# Sensors.net
KiCad netlist of a schematic drawn in Altium Designer
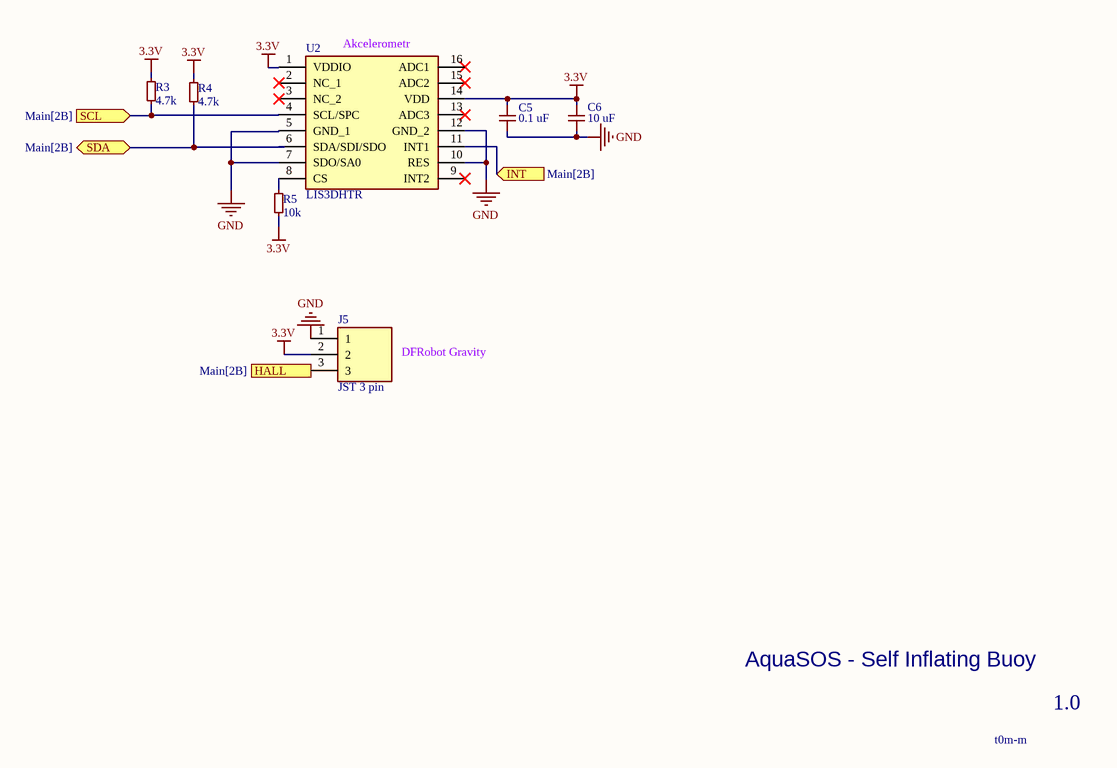
[diagram p0: Sensors.SchDoc]

(export (version "E")
  (design (tool "Eeschema 10.0.6"))
  (components
    (comp (ref "C5")
      (value "0.1 uF")
      (footprint "MLASU105SB7104KFNB25")
      (description "0.1uF Capacitor")
      (libsource (lib "Schlib1") (part "MLASU105SB7104KFNB25"))
    )
    (comp (ref "C6")
      (value "10 uF")
      (footprint "KGM05CS60J106MH")
      (description "10 uF Capacitor")
      (libsource (lib "Schlib1") (part "KGM05CS60J106MH"))
    )
    (comp (ref "J5")
      (value "JST 3 pin")
      (footprint "S3B-PH-K-S")
      (description "JST 3 pin connector")
      (libsource (lib "AquaSOS DevBoard") (part "JST 3 pin"))
    )
    (comp (ref "R3")
      (value "4.7k")
      (footprint "CRCW040210K0FKEDC")
      (description "4.7k 0402 resistor")
      (libsource (lib "") (part "RC0402FR-7D4K7L_1"))
    )
    (comp (ref "R4")
      (value "4.7k")
      (footprint "CRCW040210K0FKEDC")
      (description "4.7k 0402 resistor")
      (libsource (lib "AquaSOS DevBoard") (part "RC0402FR-7D4K7L"))
    )
    (comp (ref "R5")
      (value "10k")
      (footprint "CRCW040210K0FKEDC")
      (description "10k 0402 Resistor")
      (libsource (lib "AquaSOS DevBoard") (part "CRCW040210K0FKEDC"))
    )
    (comp (ref "U2")
      (value "LIS3DHTR")
      (footprint "LIS3DHTR")
      (fields (field (name "MOUSER PART NUMBER") "511-LIS3DHTR"))
      (libsource (lib "Schlib1") (part "LIS3DHTR"))
    )
  )
  (nets
    (net (code "1") (name "/HALL") (class "Default")
      (node (ref "J5") (pin "3") (pinfunction "3_3") (pintype "passive"))
    )
    (net (code "2") (name "/INT") (class "Default")
      (node (ref "U2") (pin "11") (pinfunction "INT1_11") (pintype "passive"))
    )
    (net (code "3") (name "/SCL") (class "Default")
      (node (ref "R3") (pin "2") (pinfunction "2_2") (pintype "passive"))
      (node (ref "U2") (pin "4") (pinfunction "SCL/SPC_4") (pintype "passive"))
    )
    (net (code "4") (name "/SDA") (class "Default")
      (node (ref "R4") (pin "1") (pinfunction "1_1") (pintype "passive"))
      (node (ref "U2") (pin "6") (pinfunction "SDA/SDI/SDO_6") (pintype "passive"))
    )
    (net (code "5") (name "3.3V") (class "Default")
      (node (ref "C5") (pin "1") (pinfunction "1_1") (pintype "passive"))
      (node (ref "C6") (pin "1") (pinfunction "1_1") (pintype "passive"))
      (node (ref "J5") (pin "2") (pinfunction "2_2") (pintype "passive"))
      (node (ref "R3") (pin "1") (pinfunction "1_1") (pintype "passive"))
      (node (ref "R4") (pin "2") (pinfunction "2_2") (pintype "passive"))
      (node (ref "R5") (pin "2") (pinfunction "2_2") (pintype "passive"))
      (node (ref "U2") (pin "1") (pinfunction "VDDIO_1") (pintype "power_in"))
      (node (ref "U2") (pin "14") (pinfunction "VDD_14") (pintype "power_in"))
    )
    (net (code "6") (name "GND") (class "Default")
      (node (ref "C5") (pin "2") (pinfunction "2_2") (pintype "passive"))
      (node (ref "C6") (pin "2") (pinfunction "2_2") (pintype "passive"))
      (node (ref "J5") (pin "1") (pinfunction "1_1") (pintype "passive"))
      (node (ref "U2") (pin "10") (pinfunction "RES_10") (pintype "passive"))
      (node (ref "U2") (pin "12") (pinfunction "GND_2_12") (pintype "passive"))
      (node (ref "U2") (pin "5") (pinfunction "GND_1_5") (pintype "passive"))
      (node (ref "U2") (pin "7") (pinfunction "SDO/SA0_7") (pintype "passive"))
    )
    (net (code "7") (name "Net-(U2-CS)") (class "Default")
      (node (ref "R5") (pin "1") (pinfunction "1_1") (pintype "passive"))
      (node (ref "U2") (pin "8") (pinfunction "CS_8") (pintype "passive"))
    )
    (net (code "8") (name "unconnected-(U2-ADC1-Pad16)") (class "Default")
      (node (ref "U2") (pin "16") (pinfunction "ADC1_16") (pintype "passive+no_connect"))
    )
    (net (code "9") (name "unconnected-(U2-ADC2-Pad15)") (class "Default")
      (node (ref "U2") (pin "15") (pinfunction "ADC2_15") (pintype "passive+no_connect"))
    )
    (net (code "10") (name "unconnected-(U2-ADC3-Pad13)") (class "Default")
      (node (ref "U2") (pin "13") (pinfunction "ADC3_13") (pintype "passive+no_connect"))
    )
    (net (code "11") (name "unconnected-(U2-INT2-Pad9)") (class "Default")
      (node (ref "U2") (pin "9") (pinfunction "INT2_9") (pintype "passive+no_connect"))
    )
    (net (code "12") (name "unconnected-(U2-NC_1-Pad2)") (class "Default")
      (node (ref "U2") (pin "2") (pinfunction "NC_1_2") (pintype "passive+no_connect"))
    )
    (net (code "13") (name "unconnected-(U2-NC_2-Pad3)") (class "Default")
      (node (ref "U2") (pin "3") (pinfunction "NC_2_3") (pintype "passive+no_connect"))
    )
  )
)
